# Sheet1.net
KiCad netlist of a schematic drawn in Altium Designer
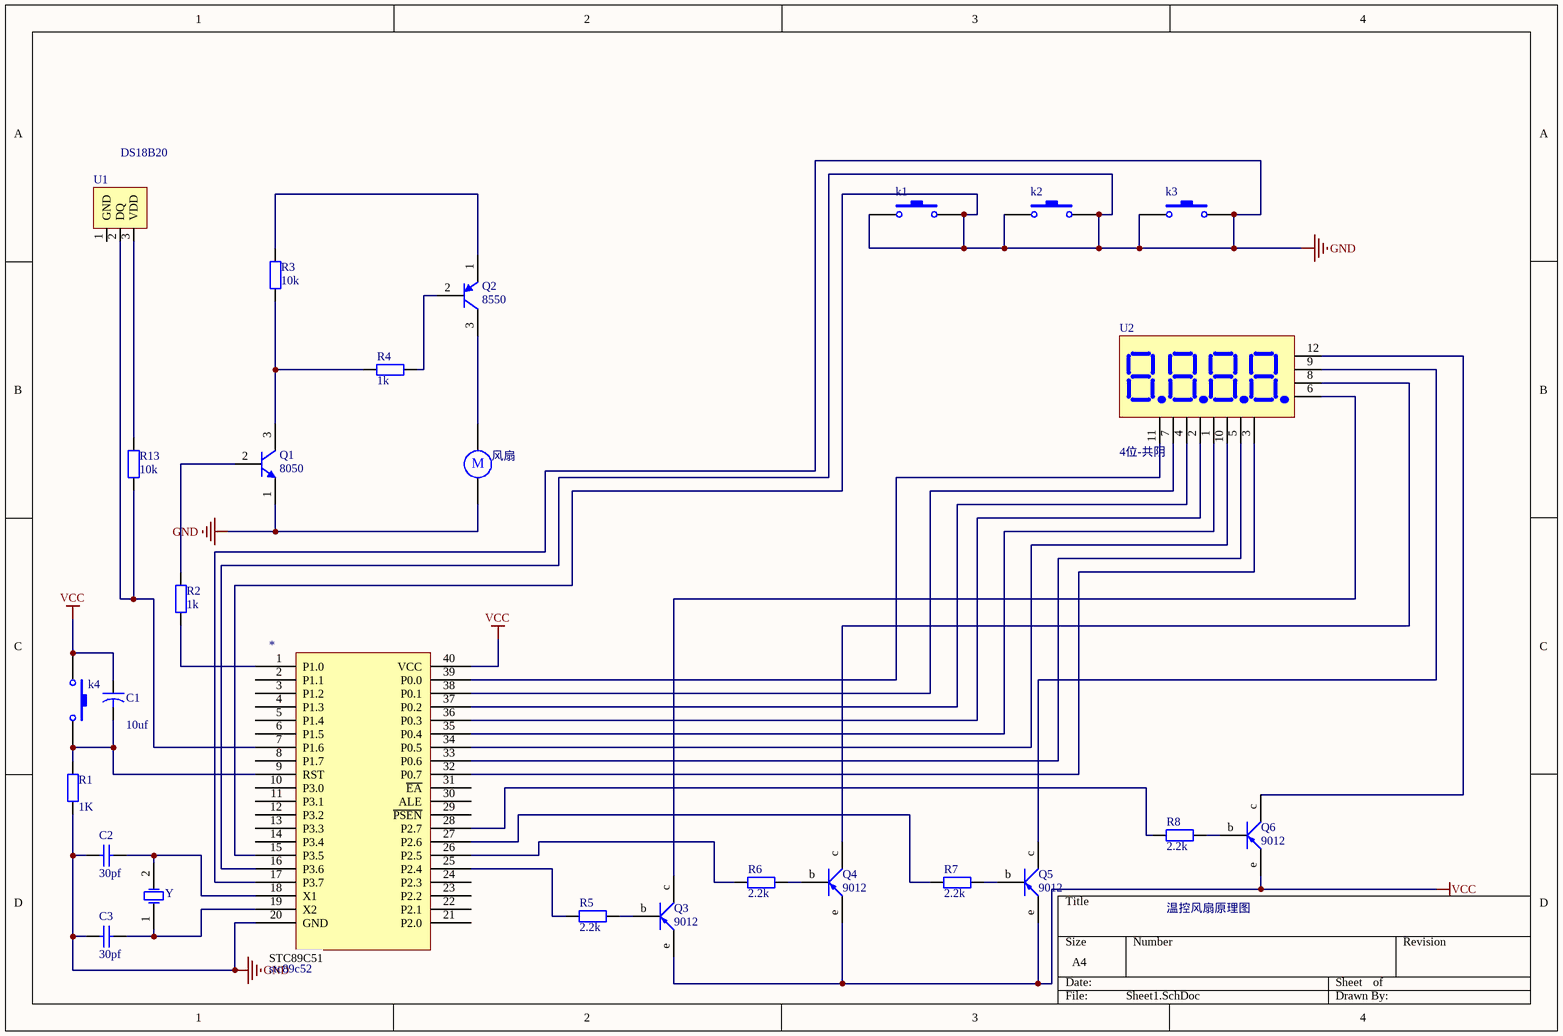
[diagram p0: Sheet1.SchDoc]

(export (version "E")
  (design (tool "Eeschema 10.0.6"))
  (components
    (comp (ref "*")
      (value "stc89c52")
      (footprint "stc89c52:stc89c52")
      (libsource (lib "stc89c52") (part "stc89c52"))
    )
    (comp (ref "C1")
      (value "10uf")
      (footprint "CAPR5-4X5")
      (description "Capacitor")
      (fields (field (name "Comment") "Cap2") (field (name "PUBLISHER") "Altium Limited"))
      (libsource (lib "Miscellaneous Devices") (part "Cap2"))
    )
    (comp (ref "C2")
      (value "30pf")
      (footprint "1206_C")
      (description "1206贴片电容")
      (libsource (lib "02 Miscellaneous_Devices_ZSF_Library") (part "Cap_1206"))
    )
    (comp (ref "C3")
      (value "30pf")
      (footprint "1206_C")
      (description "1206贴片电容")
      (libsource (lib "02 Miscellaneous_Devices_ZSF_Library") (part "Cap_1206"))
    )
    (comp (ref "k1")
      (value "Tactile Switch")
      (footprint "BUTTON_6*6")
      (description "Tactile Switch触觉开关")
      (fields (field (name "PUBLISHER") "Altium Limited"))
      (libsource (lib "02 Miscellaneous_Devices_ZSF_Library") (part "SW-PB"))
    )
    (comp (ref "k2")
      (value "Tactile Switch")
      (footprint "BUTTON_6*6")
      (description "Tactile Switch触觉开关")
      (fields (field (name "PUBLISHER") "Altium Limited"))
      (libsource (lib "02 Miscellaneous_Devices_ZSF_Library") (part "SW-PB"))
    )
    (comp (ref "k3")
      (value "Tactile Switch")
      (footprint "BUTTON_6*6")
      (description "Tactile Switch触觉开关")
      (fields (field (name "PUBLISHER") "Altium Limited"))
      (libsource (lib "02 Miscellaneous_Devices_ZSF_Library") (part "SW-PB"))
    )
    (comp (ref "k4")
      (value "Tactile Switch")
      (footprint "BUTTON_6*6")
      (description "Tactile Switch触觉开关")
      (fields (field (name "PUBLISHER") "Altium Limited"))
      (libsource (lib "02 Miscellaneous_Devices_ZSF_Library") (part "SW-PB"))
    )
    (comp (ref "Q1")
      (value "8050")
      (footprint "TO-92(TO-92-3)")
      (description "NPN型小功率三极管")
      (libsource (lib "02 Miscellaneous_Devices_ZSF_Library") (part "8050_TO-92"))
    )
    (comp (ref "Q2")
      (value "8550")
      (footprint "TO-92(TO-92-3)")
      (description "PNP型小功率三极管")
      (libsource (lib "02 Miscellaneous_Devices_ZSF_Library") (part "8550_TO-92"))
    )
    (comp (ref "Q3") (value "9012") (footprint "PNP") (libsource (lib "*") (part "PNP")))
    (comp (ref "Q4") (value "9012") (footprint "PNP") (libsource (lib "*") (part "PNP")))
    (comp (ref "Q5") (value "9012") (footprint "PNP") (libsource (lib "*") (part "PNP")))
    (comp (ref "Q6") (value "9012") (footprint "PNP") (libsource (lib "*") (part "PNP")))
    (comp (ref "R1")
      (value "1K")
      (footprint "AXIAL-0.4")
      (description "Resistor")
      (fields (field (name "Comment") "Res2") (field (name "PUBLISHER") "Altium Limited"))
      (libsource (lib "Miscellaneous Devices") (part "Res2"))
    )
    (comp (ref "R2")
      (value "1k")
      (footprint "AXIAL-0.6-R")
      (description "Resistor 直插电阻 1W")
      (fields (field (name "PUBLISHER") "Altium Limited"))
      (libsource (lib "02 Miscellaneous_Devices_ZSF_Library") (part "Res2_1W"))
    )
    (comp (ref "R3")
      (value "10k")
      (footprint "AXIAL-0.6-R")
      (description "Resistor 直插电阻 1W")
      (fields (field (name "PUBLISHER") "Altium Limited"))
      (libsource (lib "02 Miscellaneous_Devices_ZSF_Library") (part "Res2_1W"))
    )
    (comp (ref "R4")
      (value "1k")
      (footprint "AXIAL-0.6-R")
      (description "Resistor 直插电阻 1W")
      (fields (field (name "PUBLISHER") "Altium Limited"))
      (libsource (lib "") (part "Res2_1W_1"))
    )
    (comp (ref "R5")
      (value "2.2k")
      (footprint "AXIAL-0.8-R")
      (description "Resistor 直插电阻 2W")
      (fields (field (name "PUBLISHER") "Altium Limited"))
      (libsource (lib "02 Miscellaneous_Devices_ZSF_Library") (part "Res2_2W"))
    )
    (comp (ref "R6")
      (value "2.2k")
      (footprint "AXIAL-0.8-R")
      (description "Resistor 直插电阻 2W")
      (fields (field (name "PUBLISHER") "Altium Limited"))
      (libsource (lib "02 Miscellaneous_Devices_ZSF_Library") (part "Res2_2W"))
    )
    (comp (ref "R7")
      (value "2.2k")
      (footprint "AXIAL-0.8-R")
      (description "Resistor 直插电阻 2W")
      (fields (field (name "PUBLISHER") "Altium Limited"))
      (libsource (lib "02 Miscellaneous_Devices_ZSF_Library") (part "Res2_2W"))
    )
    (comp (ref "R8")
      (value "2.2k")
      (footprint "AXIAL-0.8-R")
      (description "Resistor 直插电阻 2W")
      (fields (field (name "PUBLISHER") "Altium Limited"))
      (libsource (lib "02 Miscellaneous_Devices_ZSF_Library") (part "Res2_2W"))
    )
    (comp (ref "R13")
      (value "10k")
      (footprint "AXIAL-0.6-R")
      (description "Resistor 直插电阻 1W")
      (fields (field (name "PUBLISHER") "Altium Limited"))
      (libsource (lib "02 Miscellaneous_Devices_ZSF_Library") (part "Res2_1W"))
    )
    (comp (ref "U1")
      (value "DS18B20")
      (libsource (lib "02 Miscellaneous_Devices_ZSF_Library") (part "DS18B20"))
    )
    (comp (ref "U2")
      (value "4位-共阴")
      (footprint "SEG4_3641")
      (description "4位一体共阳数码管 0.36英寸30mm*14mm*7.2mm")
      (libsource (lib "02 Miscellaneous_Devices_ZSF_Library") (part "4位-共阳"))
    )
    (comp (ref "Y")
      (value "XTAL")
      (footprint "R38")
      (description "Crystal Oscillator")
      (fields (field (name "PUBLISHER") "Altium Limited"))
      (libsource (lib "Miscellaneous Devices") (part "XTAL"))
    )
    (comp (ref "风扇")
      (value "Motor")
      (footprint "RB5-10.5")
      (description "Motor, General Kind")
      (fields (field (name "PUBLISHER") "Altium Limited"))
      (libsource (lib "Miscellaneous Devices") (part "Motor"))
    )
  )
  (nets
    (net (code "1") (name "GND") (class "Default")
      (node (ref "*") (pin "15") (pinfunction "P3.5_15") (pintype "passive"))
      (node (ref "*") (pin "16") (pinfunction "P3.6_16") (pintype "passive"))
      (node (ref "*") (pin "17") (pinfunction "P3.7_17") (pintype "passive"))
      (node (ref "*") (pin "20") (pinfunction "GND_20") (pintype "passive"))
      (node (ref "C2") (pin "1") (pinfunction "1_1") (pintype "passive"))
      (node (ref "C3") (pin "1") (pinfunction "1_1") (pintype "passive"))
      (node (ref "Q1") (pin "1") (pinfunction "E_1") (pintype "passive"))
      (node (ref "R1") (pin "1") (pinfunction "1_1") (pintype "passive"))
      (node (ref "k1") (pin "1") (pinfunction "1_1") (pintype "passive"))
      (node (ref "k1") (pin "2") (pinfunction "2_2") (pintype "passive"))
      (node (ref "k2") (pin "1") (pinfunction "1_1") (pintype "passive"))
      (node (ref "k2") (pin "2") (pinfunction "2_2") (pintype "passive"))
      (node (ref "k3") (pin "1") (pinfunction "1_1") (pintype "passive"))
      (node (ref "k3") (pin "2") (pinfunction "2_2") (pintype "passive"))
      (node (ref "风扇") (pin "2") (pinfunction "2_2") (pintype "passive"))
    )
    (net (code "2") (name "Net-(*-P0.0)") (class "Default")
      (node (ref "*") (pin "39") (pinfunction "P0.0_39") (pintype "passive"))
      (node (ref "U2") (pin "11") (pinfunction "a_11") (pintype "passive"))
    )
    (net (code "3") (name "Net-(*-P0.1)") (class "Default")
      (node (ref "*") (pin "38") (pinfunction "P0.1_38") (pintype "passive"))
      (node (ref "U2") (pin "7") (pinfunction "b_7") (pintype "passive"))
    )
    (net (code "4") (name "Net-(*-P0.2)") (class "Default")
      (node (ref "*") (pin "37") (pinfunction "P0.2_37") (pintype "passive"))
      (node (ref "U2") (pin "4") (pinfunction "c_4") (pintype "passive"))
    )
    (net (code "5") (name "Net-(*-P0.3)") (class "Default")
      (node (ref "*") (pin "36") (pinfunction "P0.3_36") (pintype "passive"))
      (node (ref "U2") (pin "2") (pinfunction "d_2") (pintype "passive"))
    )
    (net (code "6") (name "Net-(*-P0.4)") (class "Default")
      (node (ref "*") (pin "35") (pinfunction "P0.4_35") (pintype "passive"))
      (node (ref "U2") (pin "1") (pinfunction "e_1") (pintype "passive"))
    )
    (net (code "7") (name "Net-(*-P0.5)") (class "Default")
      (node (ref "*") (pin "34") (pinfunction "P0.5_34") (pintype "passive"))
      (node (ref "U2") (pin "10") (pinfunction "f_10") (pintype "passive"))
    )
    (net (code "8") (name "Net-(*-P0.6)") (class "Default")
      (node (ref "*") (pin "33") (pinfunction "P0.6_33") (pintype "passive"))
      (node (ref "U2") (pin "5") (pinfunction "g_5") (pintype "passive"))
    )
    (net (code "9") (name "Net-(*-P0.7)") (class "Default")
      (node (ref "*") (pin "32") (pinfunction "P0.7_32") (pintype "passive"))
      (node (ref "U2") (pin "3") (pinfunction "dp_3") (pintype "passive"))
    )
    (net (code "10") (name "Net-(*-P1.0)") (class "Default")
      (node (ref "*") (pin "1") (pinfunction "P1.0_1") (pintype "passive"))
      (node (ref "R2") (pin "1") (pinfunction "1_1") (pintype "passive"))
    )
    (net (code "11") (name "Net-(*-P1.6)") (class "Default")
      (node (ref "*") (pin "7") (pinfunction "P1.6_7") (pintype "passive"))
      (node (ref "R13") (pin "1") (pinfunction "1_1") (pintype "passive"))
      (node (ref "U1") (pin "2") (pinfunction "DQ_2") (pintype "passive"))
    )
    (net (code "12") (name "Net-(*-P2.4)") (class "Default")
      (node (ref "*") (pin "25") (pinfunction "P2.4_25") (pintype "passive"))
      (node (ref "R5") (pin "1") (pinfunction "1_1") (pintype "passive"))
    )
    (net (code "13") (name "Net-(*-P2.5)") (class "Default")
      (node (ref "*") (pin "26") (pinfunction "P2.5_26") (pintype "passive"))
      (node (ref "R6") (pin "1") (pinfunction "1_1") (pintype "passive"))
    )
    (net (code "14") (name "Net-(*-P2.6)") (class "Default")
      (node (ref "*") (pin "27") (pinfunction "P2.6_27") (pintype "passive"))
      (node (ref "R7") (pin "1") (pinfunction "1_1") (pintype "passive"))
    )
    (net (code "15") (name "Net-(*-P2.7)") (class "Default")
      (node (ref "*") (pin "28") (pinfunction "P2.7_28") (pintype "passive"))
      (node (ref "R8") (pin "1") (pinfunction "1_1") (pintype "passive"))
    )
    (net (code "16") (name "Net-(*-RST)") (class "Default")
      (node (ref "*") (pin "9") (pinfunction "RST_9") (pintype "passive"))
      (node (ref "C1") (pin "2") (pinfunction "2_2") (pintype "passive"))
      (node (ref "R1") (pin "2") (pinfunction "2_2") (pintype "passive"))
      (node (ref "k4") (pin "2") (pinfunction "2_2") (pintype "passive"))
    )
    (net (code "17") (name "Net-(*-X1)") (class "Default")
      (node (ref "*") (pin "18") (pinfunction "X1_18") (pintype "passive"))
      (node (ref "C2") (pin "2") (pinfunction "2_2") (pintype "passive"))
      (node (ref "Y") (pin "2") (pinfunction "OSC2_2") (pintype "passive"))
    )
    (net (code "18") (name "Net-(*-X2)") (class "Default")
      (node (ref "*") (pin "19") (pinfunction "X2_19") (pintype "passive"))
      (node (ref "C3") (pin "2") (pinfunction "2_2") (pintype "passive"))
      (node (ref "Y") (pin "1") (pinfunction "OSC1_1") (pintype "passive"))
    )
    (net (code "19") (name "Net-(Q1-B)") (class "Default")
      (node (ref "Q1") (pin "2") (pinfunction "B_2") (pintype "passive"))
      (node (ref "R2") (pin "2") (pinfunction "2_2") (pintype "passive"))
    )
    (net (code "20") (name "Net-(Q1-C)") (class "Default")
      (node (ref "Q1") (pin "3") (pinfunction "C_3") (pintype "passive"))
      (node (ref "R3") (pin "1") (pinfunction "1_1") (pintype "passive"))
      (node (ref "R4") (pin "1") (pinfunction "1_1") (pintype "passive"))
    )
    (net (code "21") (name "Net-(Q2-B)") (class "Default")
      (node (ref "Q2") (pin "2") (pinfunction "B_2") (pintype "passive"))
      (node (ref "R4") (pin "2") (pinfunction "2_2") (pintype "passive"))
    )
    (net (code "22") (name "Net-(Q2-C)") (class "Default")
      (node (ref "Q2") (pin "3") (pinfunction "C_3") (pintype "passive"))
      (node (ref "风扇") (pin "1") (pinfunction "1_1") (pintype "passive"))
    )
    (net (code "23") (name "Net-(Q2-E)") (class "Default")
      (node (ref "Q2") (pin "1") (pinfunction "E_1") (pintype "passive"))
      (node (ref "R3") (pin "2") (pinfunction "2_2") (pintype "passive"))
    )
    (net (code "24") (name "Net-(Q3-Padb)") (class "Default")
      (node (ref "Q3") (pin "b") (pinfunction "b_b") (pintype "passive"))
      (node (ref "R5") (pin "2") (pinfunction "2_2") (pintype "passive"))
    )
    (net (code "25") (name "Net-(Q4-Padb)") (class "Default")
      (node (ref "Q4") (pin "b") (pinfunction "b_b") (pintype "passive"))
      (node (ref "R6") (pin "2") (pinfunction "2_2") (pintype "passive"))
    )
    (net (code "26") (name "Net-(Q5-Padb)") (class "Default")
      (node (ref "Q5") (pin "b") (pinfunction "b_b") (pintype "passive"))
      (node (ref "R7") (pin "2") (pinfunction "2_2") (pintype "passive"))
    )
    (net (code "27") (name "Net-(Q6-Padb)") (class "Default")
      (node (ref "Q6") (pin "b") (pinfunction "b_b") (pintype "passive"))
      (node (ref "R8") (pin "2") (pinfunction "2_2") (pintype "passive"))
    )
    (net (code "28") (name "Net-(U1-VDD)") (class "Default")
      (node (ref "R13") (pin "2") (pinfunction "2_2") (pintype "passive"))
      (node (ref "U1") (pin "3") (pinfunction "VDD_3") (pintype "passive"))
    )
    (net (code "29") (name "Net-(U2-h1)") (class "Default")
      (node (ref "Q3") (pin "c") (pinfunction "c_c") (pintype "passive"))
      (node (ref "U2") (pin "6") (pinfunction "h1_6") (pintype "passive"))
    )
    (net (code "30") (name "Net-(U2-h2)") (class "Default")
      (node (ref "Q4") (pin "c") (pinfunction "c_c") (pintype "passive"))
      (node (ref "U2") (pin "8") (pinfunction "h2_8") (pintype "passive"))
    )
    (net (code "31") (name "Net-(U2-h3)") (class "Default")
      (node (ref "Q5") (pin "c") (pinfunction "c_c") (pintype "passive"))
      (node (ref "U2") (pin "9") (pinfunction "h3_9") (pintype "passive"))
    )
    (net (code "32") (name "Net-(U2-h4)") (class "Default")
      (node (ref "Q6") (pin "c") (pinfunction "c_c") (pintype "passive"))
      (node (ref "U2") (pin "12") (pinfunction "h4_12") (pintype "passive"))
    )
    (net (code "33") (name "VCC") (class "Default")
      (node (ref "*") (pin "40") (pinfunction "VCC_40") (pintype "passive"))
      (node (ref "C1") (pin "1") (pinfunction "1_1") (pintype "passive"))
      (node (ref "Q3") (pin "e") (pinfunction "e_e") (pintype "passive"))
      (node (ref "Q4") (pin "e") (pinfunction "e_e") (pintype "passive"))
      (node (ref "Q5") (pin "e") (pinfunction "e_e") (pintype "passive"))
      (node (ref "Q6") (pin "e") (pinfunction "e_e") (pintype "passive"))
      (node (ref "k4") (pin "1") (pinfunction "1_1") (pintype "passive"))
    )
    (net (code "34") (name "unconnected-(*-ALE-Pad30)") (class "Default")
      (node (ref "*") (pin "30") (pinfunction "ALE_30") (pintype "passive"))
    )
    (net (code "35") (name "unconnected-(*-P1.1-Pad2)") (class "Default")
      (node (ref "*") (pin "2") (pinfunction "P1.1_2") (pintype "passive"))
    )
    (net (code "36") (name "unconnected-(*-P1.2-Pad3)") (class "Default")
      (node (ref "*") (pin "3") (pinfunction "P1.2_3") (pintype "passive"))
    )
    (net (code "37") (name "unconnected-(*-P1.3-Pad4)") (class "Default")
      (node (ref "*") (pin "4") (pinfunction "P1.3_4") (pintype "passive"))
    )
    (net (code "38") (name "unconnected-(*-P1.4-Pad5)") (class "Default")
      (node (ref "*") (pin "5") (pinfunction "P1.4_5") (pintype "passive"))
    )
    (net (code "39") (name "unconnected-(*-P1.5-Pad6)") (class "Default")
      (node (ref "*") (pin "6") (pinfunction "P1.5_6") (pintype "passive"))
    )
    (net (code "40") (name "unconnected-(*-P1.7-Pad8)") (class "Default")
      (node (ref "*") (pin "8") (pinfunction "P1.7_8") (pintype "passive"))
    )
    (net (code "41") (name "unconnected-(*-P2.0-Pad21)") (class "Default")
      (node (ref "*") (pin "21") (pinfunction "P2.0_21") (pintype "passive"))
    )
    (net (code "42") (name "unconnected-(*-P2.1-Pad22)") (class "Default")
      (node (ref "*") (pin "22") (pinfunction "P2.1_22") (pintype "passive"))
    )
    (net (code "43") (name "unconnected-(*-P2.2-Pad23)") (class "Default")
      (node (ref "*") (pin "23") (pinfunction "P2.2_23") (pintype "passive"))
    )
    (net (code "44") (name "unconnected-(*-P2.3-Pad24)") (class "Default")
      (node (ref "*") (pin "24") (pinfunction "P2.3_24") (pintype "passive"))
    )
    (net (code "45") (name "unconnected-(*-P3.0-Pad10)") (class "Default")
      (node (ref "*") (pin "10") (pinfunction "P3.0_10") (pintype "passive"))
    )
    (net (code "46") (name "unconnected-(*-P3.1-Pad11)") (class "Default")
      (node (ref "*") (pin "11") (pinfunction "P3.1_11") (pintype "passive"))
    )
    (net (code "47") (name "unconnected-(*-P3.2-Pad12)") (class "Default")
      (node (ref "*") (pin "12") (pinfunction "P3.2_12") (pintype "passive"))
    )
    (net (code "48") (name "unconnected-(*-P3.3-Pad13)") (class "Default")
      (node (ref "*") (pin "13") (pinfunction "P3.3_13") (pintype "passive"))
    )
    (net (code "49") (name "unconnected-(*-P3.4-Pad14)") (class "Default")
      (node (ref "*") (pin "14") (pinfunction "P3.4_14") (pintype "passive"))
    )
    (net (code "50") (name "unconnected-(*-~{EA}-Pad31)") (class "Default")
      (node (ref "*") (pin "31") (pinfunction "~{EA}_31") (pintype "passive"))
    )
    (net (code "51") (name "unconnected-(*-~{PSEN}-Pad29)") (class "Default")
      (node (ref "*") (pin "29") (pinfunction "~{PSEN}_29") (pintype "passive"))
    )
    (net (code "52") (name "unconnected-(U1-GND-Pad1)") (class "Default")
      (node (ref "U1") (pin "1") (pinfunction "GND_1") (pintype "passive"))
    )
  )
)
